# Paralelo74374_SingleDisp.net
KiCad netlist of a schematic drawn in EAGLE
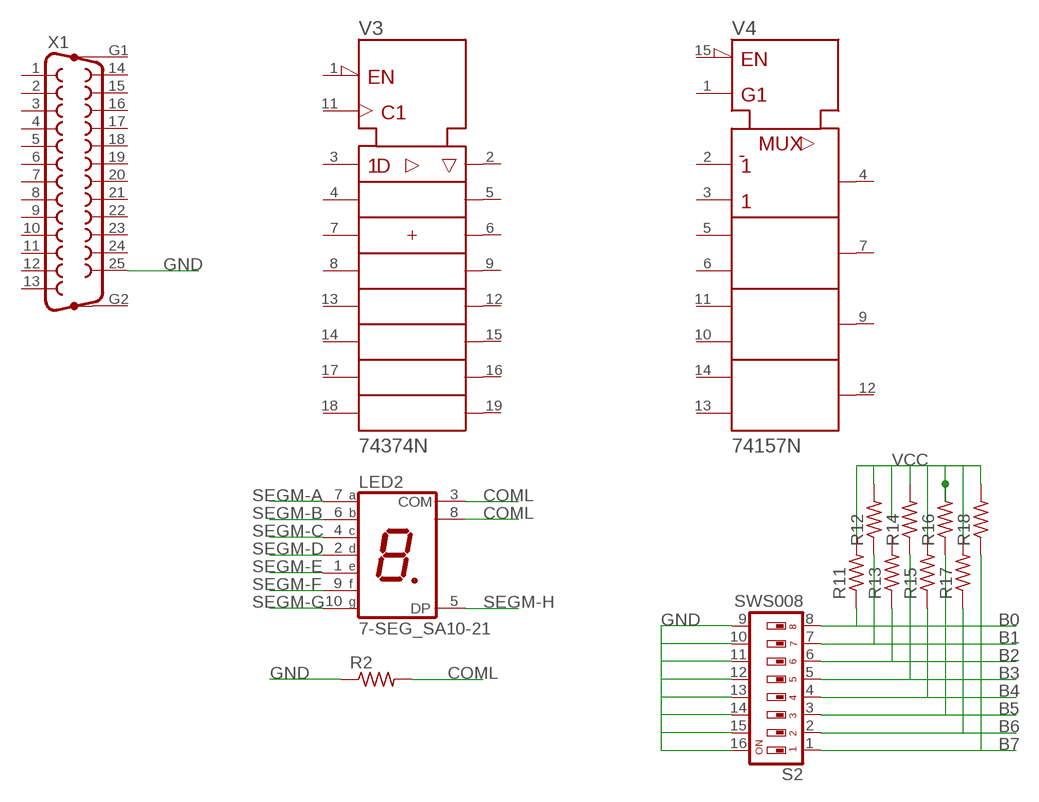
[diagram p0: schematic, sheet 1]

(export (version "E")
  (design (tool "Eeschema 10.0.6"))
  (components
    (comp (ref "LED2")
      (value "7-SEG_SA10-21")
      (footprint "eagle-import:SA10-21")
      (libsource (lib "eagle-import") (part "7-SEG_SA10-21"))
    )
    (comp (ref "R2")
      (value "R-US_0204/5")
      (footprint "eagle-import:0204_5")
      (libsource (lib "eagle-import") (part "R-US_0204/5"))
    )
    (comp (ref "R11")
      (value "R-US_0207/12")
      (footprint "eagle-import:0207_12")
      (libsource (lib "eagle-import") (part "resistor_348_R-US_0207/12"))
    )
    (comp (ref "R12")
      (value "R-US_0207/12")
      (footprint "eagle-import:0207_12")
      (libsource (lib "eagle-import") (part "resistor_348_R-US_0207/12"))
    )
    (comp (ref "R13")
      (value "R-US_0207/12")
      (footprint "eagle-import:0207_12")
      (libsource (lib "eagle-import") (part "resistor_348_R-US_0207/12"))
    )
    (comp (ref "R14")
      (value "R-US_0207/12")
      (footprint "eagle-import:0207_12")
      (libsource (lib "eagle-import") (part "resistor_348_R-US_0207/12"))
    )
    (comp (ref "R15")
      (value "R-US_0207/12")
      (footprint "eagle-import:0207_12")
      (libsource (lib "eagle-import") (part "resistor_348_R-US_0207/12"))
    )
    (comp (ref "R16")
      (value "R-US_0207/12")
      (footprint "eagle-import:0207_12")
      (libsource (lib "eagle-import") (part "resistor_348_R-US_0207/12"))
    )
    (comp (ref "R17")
      (value "R-US_0207/12")
      (footprint "eagle-import:0207_12")
      (libsource (lib "eagle-import") (part "resistor_348_R-US_0207/12"))
    )
    (comp (ref "R18")
      (value "R-US_0207/12")
      (footprint "eagle-import:0207_12")
      (libsource (lib "eagle-import") (part "resistor_348_R-US_0207/12"))
    )
    (comp (ref "S2")
      (value "SWS008")
      (footprint "eagle-import:SMS-008")
      (libsource (lib "eagle-import") (part "SWS008"))
    )
    (comp (ref "V3")
      (value "74374N")
      (footprint "eagle-import:DIL20")
      (libsource (lib "eagle-import") (part "74374N"))
    )
    (comp (ref "V4")
      (value "74157N")
      (footprint "eagle-import:DIL16")
      (libsource (lib "eagle-import") (part "74157N"))
    )
    (comp (ref "X1")
      (value "F25HP")
      (footprint "eagle-import:F25HP")
      (libsource (lib "eagle-import") (part "F25HP"))
    )
  )
  (nets
    (net (code "1") (name "/B0") (class "Default")
      (node (ref "R11") (pin "1") (pinfunction "1_1") (pintype "passive"))
      (node (ref "S2") (pin "8") (pinfunction "8_8") (pintype "passive"))
    )
    (net (code "2") (name "/B1") (class "Default")
      (node (ref "R12") (pin "1") (pinfunction "1_1") (pintype "passive"))
      (node (ref "S2") (pin "7") (pinfunction "7_7") (pintype "passive"))
    )
    (net (code "3") (name "/B2") (class "Default")
      (node (ref "R13") (pin "1") (pinfunction "1_1") (pintype "passive"))
      (node (ref "S2") (pin "6") (pinfunction "6_6") (pintype "passive"))
    )
    (net (code "4") (name "/B3") (class "Default")
      (node (ref "R14") (pin "1") (pinfunction "1_1") (pintype "passive"))
      (node (ref "S2") (pin "5") (pinfunction "5_5") (pintype "passive"))
    )
    (net (code "5") (name "/B4") (class "Default")
      (node (ref "R15") (pin "1") (pinfunction "1_1") (pintype "passive"))
      (node (ref "S2") (pin "4") (pinfunction "4_4") (pintype "passive"))
    )
    (net (code "6") (name "/B5") (class "Default")
      (node (ref "R16") (pin "1") (pinfunction "1_1") (pintype "passive"))
      (node (ref "S2") (pin "3") (pinfunction "3_3") (pintype "passive"))
    )
    (net (code "7") (name "/B6") (class "Default")
      (node (ref "R17") (pin "1") (pinfunction "1_1") (pintype "passive"))
      (node (ref "S2") (pin "2") (pinfunction "2_2") (pintype "passive"))
    )
    (net (code "8") (name "/B7") (class "Default")
      (node (ref "R18") (pin "1") (pinfunction "1_1") (pintype "passive"))
      (node (ref "S2") (pin "1") (pinfunction "1_1") (pintype "passive"))
    )
    (net (code "9") (name "/COML") (class "Default")
      (node (ref "LED2") (pin "3") (pinfunction "COM_3") (pintype "passive"))
      (node (ref "LED2") (pin "8") (pinfunction "COM_8") (pintype "passive"))
      (node (ref "R2") (pin "2") (pinfunction "2_2") (pintype "passive"))
    )
    (net (code "10") (name "/GND") (class "Default")
      (node (ref "R2") (pin "1") (pinfunction "1_1") (pintype "passive"))
      (node (ref "S2") (pin "10") (pinfunction "10_10") (pintype "passive"))
      (node (ref "S2") (pin "11") (pinfunction "11_11") (pintype "passive"))
      (node (ref "S2") (pin "12") (pinfunction "12_12") (pintype "passive"))
      (node (ref "S2") (pin "13") (pinfunction "13_13") (pintype "passive"))
      (node (ref "S2") (pin "14") (pinfunction "14_14") (pintype "passive"))
      (node (ref "S2") (pin "15") (pinfunction "15_15") (pintype "passive"))
      (node (ref "S2") (pin "16") (pinfunction "16_16") (pintype "passive"))
      (node (ref "S2") (pin "9") (pinfunction "9_9") (pintype "passive"))
      (node (ref "X1") (pin "25") (pinfunction "25_25") (pintype "passive"))
    )
    (net (code "11") (name "/SEGM-A") (class "Default")
      (node (ref "LED2") (pin "7") (pinfunction "A_7") (pintype "passive"))
    )
    (net (code "12") (name "/SEGM-B") (class "Default")
      (node (ref "LED2") (pin "6") (pinfunction "B_6") (pintype "passive"))
    )
    (net (code "13") (name "/SEGM-C") (class "Default")
      (node (ref "LED2") (pin "4") (pinfunction "C_4") (pintype "passive"))
    )
    (net (code "14") (name "/SEGM-D") (class "Default")
      (node (ref "LED2") (pin "2") (pinfunction "D_2") (pintype "passive"))
    )
    (net (code "15") (name "/SEGM-E") (class "Default")
      (node (ref "LED2") (pin "1") (pinfunction "E_1") (pintype "passive"))
    )
    (net (code "16") (name "/SEGM-F") (class "Default")
      (node (ref "LED2") (pin "9") (pinfunction "F_9") (pintype "passive"))
    )
    (net (code "17") (name "/SEGM-G") (class "Default")
      (node (ref "LED2") (pin "10") (pinfunction "G_10") (pintype "passive"))
    )
    (net (code "18") (name "/SEGM-H") (class "Default")
      (node (ref "LED2") (pin "5") (pinfunction "DP_5") (pintype "passive"))
    )
    (net (code "19") (name "/VCC") (class "Default")
      (node (ref "R11") (pin "2") (pinfunction "2_2") (pintype "passive"))
      (node (ref "R12") (pin "2") (pinfunction "2_2") (pintype "passive"))
      (node (ref "R14") (pin "2") (pinfunction "2_2") (pintype "passive"))
      (node (ref "R15") (pin "2") (pinfunction "2_2") (pintype "passive"))
      (node (ref "R16") (pin "2") (pinfunction "2_2") (pintype "passive"))
      (node (ref "R17") (pin "2") (pinfunction "2_2") (pintype "passive"))
      (node (ref "R18") (pin "2") (pinfunction "2_2") (pintype "passive"))
    )
    (net (code "20") (name "unconnected-(R13-Pad2)") (class "Default")
      (node (ref "R13") (pin "2") (pinfunction "2_2") (pintype "passive"))
    )
    (net (code "21") (name "unconnected-(V3C-1D-Pad3)") (class "Default")
      (node (ref "V3") (pin "3") (pinfunction "1D_3") (pintype "input"))
    )
    (net (code "22") (name "unconnected-(V3C-1Q-Pad2)") (class "Default")
      (node (ref "V3") (pin "2") (pinfunction "1Q_2") (pintype "tri_state"))
    )
    (net (code "23") (name "unconnected-(V3C-2D-Pad4)") (class "Default")
      (node (ref "V3") (pin "4") (pinfunction "2D_4") (pintype "input"))
    )
    (net (code "24") (name "unconnected-(V3C-2Q-Pad5)") (class "Default")
      (node (ref "V3") (pin "5") (pinfunction "2Q_5") (pintype "tri_state"))
    )
    (net (code "25") (name "unconnected-(V3C-3D-Pad7)") (class "Default")
      (node (ref "V3") (pin "7") (pinfunction "3D_7") (pintype "input"))
    )
    (net (code "26") (name "unconnected-(V3C-3Q-Pad6)") (class "Default")
      (node (ref "V3") (pin "6") (pinfunction "3Q_6") (pintype "tri_state"))
    )
    (net (code "27") (name "unconnected-(V3C-4D-Pad8)") (class "Default")
      (node (ref "V3") (pin "8") (pinfunction "4D_8") (pintype "input"))
    )
    (net (code "28") (name "unconnected-(V3C-4Q-Pad9)") (class "Default")
      (node (ref "V3") (pin "9") (pinfunction "4Q_9") (pintype "tri_state"))
    )
    (net (code "29") (name "unconnected-(V3C-5D-Pad13)") (class "Default")
      (node (ref "V3") (pin "13") (pinfunction "5D_13") (pintype "input"))
    )
    (net (code "30") (name "unconnected-(V3C-5Q-Pad12)") (class "Default")
      (node (ref "V3") (pin "12") (pinfunction "5Q_12") (pintype "tri_state"))
    )
    (net (code "31") (name "unconnected-(V3C-6D-Pad14)") (class "Default")
      (node (ref "V3") (pin "14") (pinfunction "6D_14") (pintype "input"))
    )
    (net (code "32") (name "unconnected-(V3C-6Q-Pad15)") (class "Default")
      (node (ref "V3") (pin "15") (pinfunction "6Q_15") (pintype "tri_state"))
    )
    (net (code "33") (name "unconnected-(V3C-7D-Pad17)") (class "Default")
      (node (ref "V3") (pin "17") (pinfunction "7D_17") (pintype "input"))
    )
    (net (code "34") (name "unconnected-(V3C-7Q-Pad16)") (class "Default")
      (node (ref "V3") (pin "16") (pinfunction "7Q_16") (pintype "tri_state"))
    )
    (net (code "35") (name "unconnected-(V3C-8D-Pad18)") (class "Default")
      (node (ref "V3") (pin "18") (pinfunction "8D_18") (pintype "input"))
    )
    (net (code "36") (name "unconnected-(V3C-8Q-Pad19)") (class "Default")
      (node (ref "V3") (pin "19") (pinfunction "8Q_19") (pintype "tri_state"))
    )
    (net (code "37") (name "unconnected-(V3C-CLK-Pad11)") (class "Default")
      (node (ref "V3") (pin "11") (pinfunction "CLK_11") (pintype "input"))
    )
    (net (code "38") (name "unconnected-(V3C-~{OC}-Pad1)") (class "Default")
      (node (ref "V3") (pin "1") (pinfunction "~{OC}_1") (pintype "input"))
    )
    (net (code "39") (name "unconnected-(V4C-1A-Pad2)") (class "Default")
      (node (ref "V4") (pin "2") (pinfunction "1A_2") (pintype "input"))
    )
    (net (code "40") (name "unconnected-(V4C-1B-Pad3)") (class "Default")
      (node (ref "V4") (pin "3") (pinfunction "1B_3") (pintype "input"))
    )
    (net (code "41") (name "unconnected-(V4C-1Y-Pad4)") (class "Default")
      (node (ref "V4") (pin "4") (pinfunction "1Y_4") (pintype "output"))
    )
    (net (code "42") (name "unconnected-(V4C-2A-Pad5)") (class "Default")
      (node (ref "V4") (pin "5") (pinfunction "2A_5") (pintype "input"))
    )
    (net (code "43") (name "unconnected-(V4C-2B-Pad6)") (class "Default")
      (node (ref "V4") (pin "6") (pinfunction "2B_6") (pintype "input"))
    )
    (net (code "44") (name "unconnected-(V4C-2Y-Pad7)") (class "Default")
      (node (ref "V4") (pin "7") (pinfunction "2Y_7") (pintype "output"))
    )
    (net (code "45") (name "unconnected-(V4C-3A-Pad11)") (class "Default")
      (node (ref "V4") (pin "11") (pinfunction "3A_11") (pintype "input"))
    )
    (net (code "46") (name "unconnected-(V4C-3B-Pad10)") (class "Default")
      (node (ref "V4") (pin "10") (pinfunction "3B_10") (pintype "input"))
    )
    (net (code "47") (name "unconnected-(V4C-3Y-Pad9)") (class "Default")
      (node (ref "V4") (pin "9") (pinfunction "3Y_9") (pintype "output"))
    )
    (net (code "48") (name "unconnected-(V4C-4A-Pad14)") (class "Default")
      (node (ref "V4") (pin "14") (pinfunction "4A_14") (pintype "input"))
    )
    (net (code "49") (name "unconnected-(V4C-4B-Pad13)") (class "Default")
      (node (ref "V4") (pin "13") (pinfunction "4B_13") (pintype "input"))
    )
    (net (code "50") (name "unconnected-(V4C-4Y-Pad12)") (class "Default")
      (node (ref "V4") (pin "12") (pinfunction "4Y_12") (pintype "output"))
    )
    (net (code "51") (name "unconnected-(V4C-~{A}{slash}B-Pad1)") (class "Default")
      (node (ref "V4") (pin "1") (pinfunction "~{A}/B_1") (pintype "input"))
    )
    (net (code "52") (name "unconnected-(V4C-~{G}-Pad15)") (class "Default")
      (node (ref "V4") (pin "15") (pinfunction "~{G}_15") (pintype "input"))
    )
    (net (code "53") (name "unconnected-(X1-Pad1)") (class "Default")
      (node (ref "X1") (pin "1") (pinfunction "1_1") (pintype "passive"))
    )
    (net (code "54") (name "unconnected-(X1-Pad2)") (class "Default")
      (node (ref "X1") (pin "2") (pinfunction "2_2") (pintype "passive"))
    )
    (net (code "55") (name "unconnected-(X1-Pad3)") (class "Default")
      (node (ref "X1") (pin "3") (pinfunction "3_3") (pintype "passive"))
    )
    (net (code "56") (name "unconnected-(X1-Pad4)") (class "Default")
      (node (ref "X1") (pin "4") (pinfunction "4_4") (pintype "passive"))
    )
    (net (code "57") (name "unconnected-(X1-Pad5)") (class "Default")
      (node (ref "X1") (pin "5") (pinfunction "5_5") (pintype "passive"))
    )
    (net (code "58") (name "unconnected-(X1-Pad6)") (class "Default")
      (node (ref "X1") (pin "6") (pinfunction "6_6") (pintype "passive"))
    )
    (net (code "59") (name "unconnected-(X1-Pad7)") (class "Default")
      (node (ref "X1") (pin "7") (pinfunction "7_7") (pintype "passive"))
    )
    (net (code "60") (name "unconnected-(X1-Pad8)") (class "Default")
      (node (ref "X1") (pin "8") (pinfunction "8_8") (pintype "passive"))
    )
    (net (code "61") (name "unconnected-(X1-Pad9)") (class "Default")
      (node (ref "X1") (pin "9") (pinfunction "9_9") (pintype "passive"))
    )
    (net (code "62") (name "unconnected-(X1-Pad10)") (class "Default")
      (node (ref "X1") (pin "10") (pinfunction "10_10") (pintype "passive"))
    )
    (net (code "63") (name "unconnected-(X1-Pad11)") (class "Default")
      (node (ref "X1") (pin "11") (pinfunction "11_11") (pintype "passive"))
    )
    (net (code "64") (name "unconnected-(X1-Pad12)") (class "Default")
      (node (ref "X1") (pin "12") (pinfunction "12_12") (pintype "passive"))
    )
    (net (code "65") (name "unconnected-(X1-Pad13)") (class "Default")
      (node (ref "X1") (pin "13") (pinfunction "13_13") (pintype "passive"))
    )
    (net (code "66") (name "unconnected-(X1-Pad14)") (class "Default")
      (node (ref "X1") (pin "14") (pinfunction "14_14") (pintype "passive"))
    )
    (net (code "67") (name "unconnected-(X1-Pad15)") (class "Default")
      (node (ref "X1") (pin "15") (pinfunction "15_15") (pintype "passive"))
    )
    (net (code "68") (name "unconnected-(X1-Pad16)") (class "Default")
      (node (ref "X1") (pin "16") (pinfunction "16_16") (pintype "passive"))
    )
    (net (code "69") (name "unconnected-(X1-Pad17)") (class "Default")
      (node (ref "X1") (pin "17") (pinfunction "17_17") (pintype "passive"))
    )
    (net (code "70") (name "unconnected-(X1-Pad18)") (class "Default")
      (node (ref "X1") (pin "18") (pinfunction "18_18") (pintype "passive"))
    )
    (net (code "71") (name "unconnected-(X1-Pad19)") (class "Default")
      (node (ref "X1") (pin "19") (pinfunction "19_19") (pintype "passive"))
    )
    (net (code "72") (name "unconnected-(X1-Pad20)") (class "Default")
      (node (ref "X1") (pin "20") (pinfunction "20_20") (pintype "passive"))
    )
    (net (code "73") (name "unconnected-(X1-Pad21)") (class "Default")
      (node (ref "X1") (pin "21") (pinfunction "21_21") (pintype "passive"))
    )
    (net (code "74") (name "unconnected-(X1-Pad22)") (class "Default")
      (node (ref "X1") (pin "22") (pinfunction "22_22") (pintype "passive"))
    )
    (net (code "75") (name "unconnected-(X1-Pad23)") (class "Default")
      (node (ref "X1") (pin "23") (pinfunction "23_23") (pintype "passive"))
    )
    (net (code "76") (name "unconnected-(X1-Pad24)") (class "Default")
      (node (ref "X1") (pin "24") (pinfunction "24_24") (pintype "passive"))
    )
    (net (code "77") (name "unconnected-(X1-PadG1)") (class "Default")
      (node (ref "X1") (pin "G1") (pinfunction "G1_G1") (pintype "passive"))
    )
    (net (code "78") (name "unconnected-(X1-PadG2)") (class "Default")
      (node (ref "X1") (pin "G2") (pinfunction "G2_G2") (pintype "passive"))
    )
  )
)
